# LoRA_RA02.net
KiCad netlist of a schematic drawn in Altium Designer
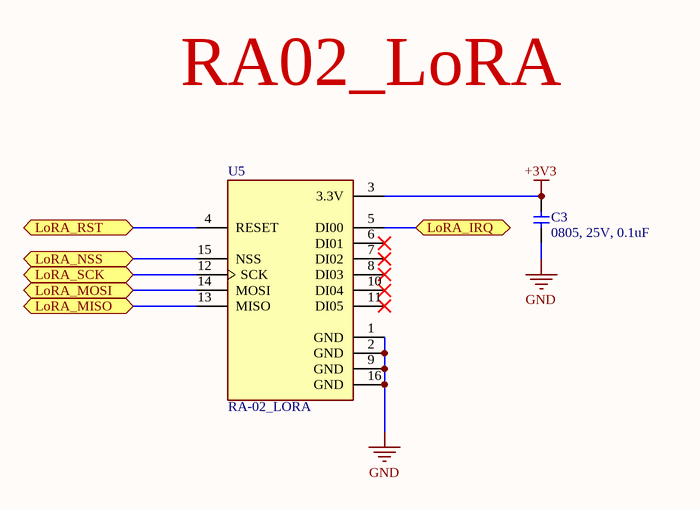
[diagram p0: LoRA_RA02.SchDoc]

(export (version "E")
  (design (tool "Eeschema 10.0.6"))
  (components
    (comp (ref "C3")
      (value "0805, 25V, 0.1uF")
      (footprint "C0805")
      (description "C0805")
      (libsource (lib "STM32F103 Blue Pill Library") (part "C0805"))
    )
    (comp (ref "U5")
      (value "RA-02_LORA")
      (footprint "MODULE_RA-02_LORA - duplicate")
      (description "Ra-02 LoRa RF M5Stack Platform Evaluation Expansion Board")
      (libsource (lib "ESP_LoRa_schematic_lib") (part "RA-02_LORA"))
    )
  )
  (nets
    (net (code "1") (name "+3V3") (class "Default")
      (node (ref "C3") (pin "2") (pinfunction "2_2") (pintype "passive"))
      (node (ref "U5") (pin "3") (pinfunction "3.3V_3") (pintype "passive"))
    )
    (net (code "2") (name "/LoRA_IRQ") (class "Default")
      (node (ref "U5") (pin "5") (pinfunction "DI00_5") (pintype "passive"))
    )
    (net (code "3") (name "/LoRA_MISO") (class "Default")
      (node (ref "U5") (pin "13") (pinfunction "MISO_13") (pintype "passive"))
    )
    (net (code "4") (name "/LoRA_MOSI") (class "Default")
      (node (ref "U5") (pin "14") (pinfunction "MOSI_14") (pintype "passive"))
    )
    (net (code "5") (name "/LoRA_NSS") (class "Default")
      (node (ref "U5") (pin "15") (pinfunction "NSS_15") (pintype "passive"))
    )
    (net (code "6") (name "/LoRA_RST") (class "Default")
      (node (ref "U5") (pin "4") (pinfunction "RESET_4") (pintype "passive"))
    )
    (net (code "7") (name "/LoRA_SCK") (class "Default")
      (node (ref "U5") (pin "12") (pinfunction "SCK_12") (pintype "passive"))
    )
    (net (code "8") (name "GND") (class "Default")
      (node (ref "C3") (pin "1") (pinfunction "1_1") (pintype "passive"))
      (node (ref "U5") (pin "1") (pinfunction "GND_1") (pintype "passive"))
      (node (ref "U5") (pin "16") (pinfunction "GND_16") (pintype "passive"))
      (node (ref "U5") (pin "2") (pinfunction "GND_2") (pintype "passive"))
      (node (ref "U5") (pin "9") (pinfunction "GND_9") (pintype "passive"))
    )
    (net (code "9") (name "unconnected-(U5-DI01-Pad6)") (class "Default")
      (node (ref "U5") (pin "6") (pinfunction "DI01_6") (pintype "passive+no_connect"))
    )
    (net (code "10") (name "unconnected-(U5-DI02-Pad7)") (class "Default")
      (node (ref "U5") (pin "7") (pinfunction "DI02_7") (pintype "passive+no_connect"))
    )
    (net (code "11") (name "unconnected-(U5-DI03-Pad8)") (class "Default")
      (node (ref "U5") (pin "8") (pinfunction "DI03_8") (pintype "passive+no_connect"))
    )
    (net (code "12") (name "unconnected-(U5-DI04-Pad10)") (class "Default")
      (node (ref "U5") (pin "10") (pinfunction "DI04_10") (pintype "passive+no_connect"))
    )
    (net (code "13") (name "unconnected-(U5-DI05-Pad11)") (class "Default")
      (node (ref "U5") (pin "11") (pinfunction "DI05_11") (pintype "passive+no_connect"))
    )
  )
)
